# Schematic.net
KiCad netlist of a schematic drawn in EAGLE
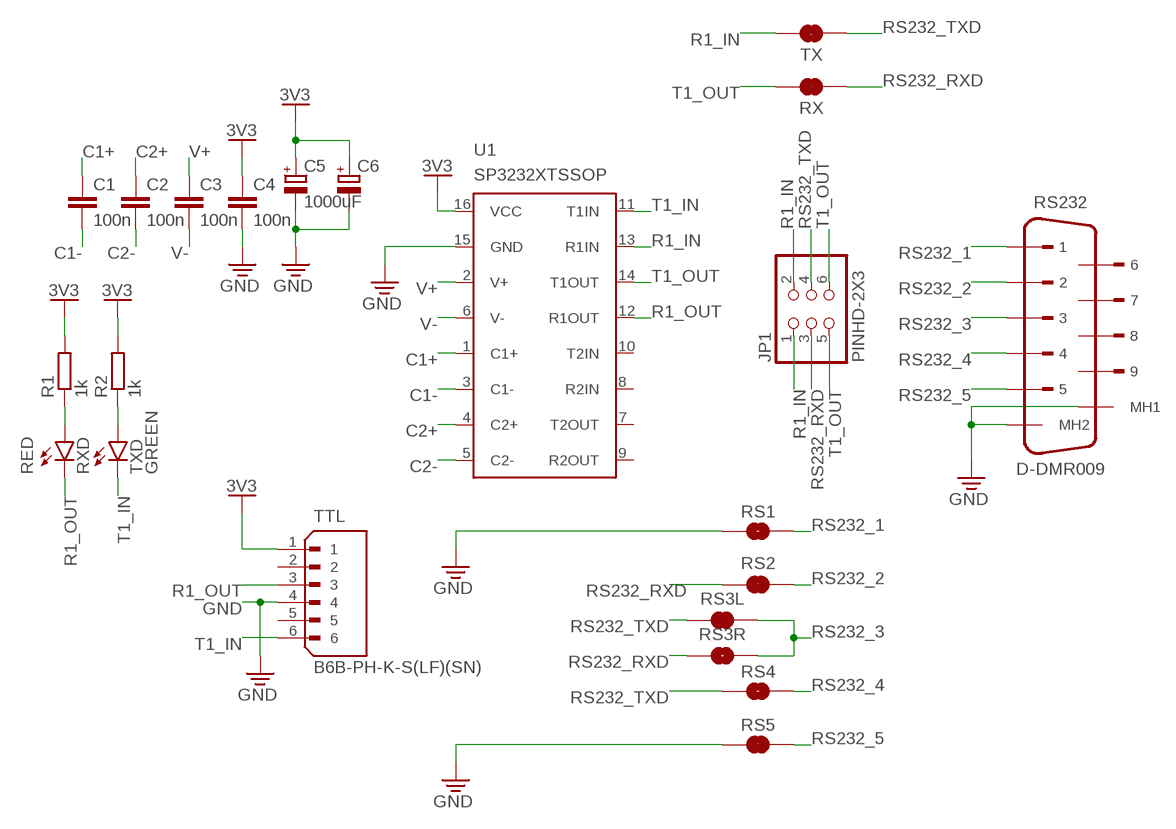
[diagram p0: schematic, sheet 1]

(export (version "E")
  (design (tool "Eeschema 10.0.6"))
  (components
    (comp (ref "C1")
      (value "100n")
      (footprint "eagle-import:C0402")
      (libsource (lib "eagle-import") (part "C-EUC0402"))
    )
    (comp (ref "C2")
      (value "100n")
      (footprint "eagle-import:C0402")
      (libsource (lib "eagle-import") (part "C-EUC0402"))
    )
    (comp (ref "C3")
      (value "100n")
      (footprint "eagle-import:C0402")
      (libsource (lib "eagle-import") (part "C-EUC0402"))
    )
    (comp (ref "C4")
      (value "100n")
      (footprint "eagle-import:C0402")
      (libsource (lib "eagle-import") (part "C-EUC0402"))
    )
    (comp (ref "C5")
      (value "1000uF")
      (footprint "eagle-import:140CLH-1010")
      (libsource (lib "eagle-import") (part "CPOL-EU140CLH-1010"))
    )
    (comp (ref "C6")
      (value "C-POL_RADIAL-11MM-DIA")
      (footprint "eagle-import:CAPPRD508W65D1000H1100B")
      (libsource (lib "eagle-import") (part "C-POLRADIAL-11MM-DIA_"))
    )
    (comp (ref "JP1")
      (value "PINHD-2X3")
      (footprint "eagle-import:2X03")
      (fields (field (name "MANUFACTURER") "Generic"))
      (libsource (lib "eagle-import") (part "PINHD-2X3"))
    )
    (comp (ref "R1")
      (value "1k")
      (footprint "eagle-import:R0402")
      (libsource (lib "eagle-import") (part "R-EU_R0402"))
    )
    (comp (ref "R2")
      (value "1k")
      (footprint "eagle-import:R0402")
      (libsource (lib "eagle-import") (part "R-EU_R0402"))
    )
    (comp (ref "RS1")
      (value "JUMPER-SMT_2_NO_SILK")
      (footprint "eagle-import:SMT-JUMPER_2_NO_SILK")
      (libsource (lib "eagle-import") (part "JUMPER-SMT_2_NO_SILK"))
    )
    (comp (ref "RS2")
      (value "JUMPER-SMT_2_NO_SILK")
      (footprint "eagle-import:SMT-JUMPER_2_NC_TRACE_SILK")
      (libsource (lib "eagle-import") (part "JUMPER-SMT_2_NC_TRACE_SILK"))
    )
    (comp (ref "RS3L")
      (value "JUMPER-SMT_2_NC_TRACE_SILK")
      (footprint "eagle-import:SMT-JUMPER_2_NC_TRACE_SILK")
      (libsource (lib "eagle-import") (part "JUMPER-SMT_2_NC_TRACE_SILK"))
    )
    (comp (ref "RS3R")
      (value "JUMPER-SMT_2_NC_TRACE_SILK")
      (footprint "eagle-import:SMT-JUMPER_2_NO_SILK")
      (libsource (lib "eagle-import") (part "JUMPER-SMT_2_NO_SILK"))
    )
    (comp (ref "RS4")
      (value "JUMPER-SMT_2_NO_SILK")
      (footprint "eagle-import:SMT-JUMPER_2_NO_SILK")
      (libsource (lib "eagle-import") (part "JUMPER-SMT_2_NO_SILK"))
    )
    (comp (ref "RS5")
      (value "JUMPER-SMT_2_NO_SILK")
      (footprint "eagle-import:SMT-JUMPER_2_NC_TRACE_SILK")
      (libsource (lib "eagle-import") (part "JUMPER-SMT_2_NC_TRACE_SILK"))
    )
    (comp (ref "RS232")
      (value "D-DMR009")
      (footprint "eagle-import:5747840-4")
      (fields (field (name "MANUFACTURER") "TE Connectivity") (field (name "MPN") "5747840-4"))
      (libsource (lib "eagle-import") (part "5747840{dblquote}"))
    )
    (comp (ref "RX")
      (value "JUMPER-SMT_2_NC_TRACE_SILK")
      (footprint "eagle-import:SMT-JUMPER_2_NC_TRACE_SILK")
      (libsource (lib "eagle-import") (part "JUMPER-SMT_2_NC_TRACE_SILK"))
    )
    (comp (ref "RXD")
      (value "RED")
      (footprint "eagle-import:CHIP-LED0603")
      (libsource (lib "eagle-import") (part "LEDCHIP-LED0603"))
    )
    (comp (ref "TTL")
      (value "B6B-PH-K-S(LF)(SN)")
      (footprint "eagle-import:JST_B6B-PH-K-S(LF)(SN)")
      (fields (field (name "MF") "JST Sales America Inc."))
      (libsource (lib "eagle-import") (part "B6B-PH-K-S(LF)(SN)"))
    )
    (comp (ref "TX")
      (value "JUMPER-SMT_2_NC_TRACE_SILK")
      (footprint "eagle-import:SMT-JUMPER_2_NC_TRACE_SILK")
      (libsource (lib "eagle-import") (part "JUMPER-SMT_2_NC_TRACE_SILK"))
    )
    (comp (ref "TXD")
      (value "GREEN")
      (footprint "eagle-import:CHIP-LED0603")
      (libsource (lib "eagle-import") (part "LEDCHIP-LED0603"))
    )
    (comp (ref "U1")
      (value "SP3232XTSSOP")
      (footprint "eagle-import:TSSOP16")
      (libsource (lib "eagle-import") (part "SP3232XTSSOP"))
    )
  )
  (nets
    (net (code "1") (name "/C1+") (class "Default")
      (node (ref "C1") (pin "1") (pinfunction "1_1") (pintype "passive"))
      (node (ref "U1") (pin "1") (pinfunction "C1+_1") (pintype "bidirectional"))
    )
    (net (code "2") (name "/C1-") (class "Default")
      (node (ref "C1") (pin "2") (pinfunction "2_2") (pintype "passive"))
      (node (ref "U1") (pin "3") (pinfunction "C1-_3") (pintype "bidirectional"))
    )
    (net (code "3") (name "/C2+") (class "Default")
      (node (ref "C2") (pin "1") (pinfunction "1_1") (pintype "passive"))
      (node (ref "U1") (pin "4") (pinfunction "C2+_4") (pintype "bidirectional"))
    )
    (net (code "4") (name "/C2-") (class "Default")
      (node (ref "C2") (pin "2") (pinfunction "2_2") (pintype "passive"))
      (node (ref "U1") (pin "5") (pinfunction "C2-_5") (pintype "bidirectional"))
    )
    (net (code "5") (name "/R1_IN") (class "Default")
      (node (ref "JP1") (pin "1") (pinfunction "1_1") (pintype "passive"))
      (node (ref "JP1") (pin "2") (pinfunction "2_2") (pintype "passive"))
      (node (ref "TX") (pin "2") (pinfunction "2_2") (pintype "passive"))
      (node (ref "U1") (pin "13") (pinfunction "R1IN_13") (pintype "input"))
    )
    (net (code "6") (name "/R1_OUT") (class "Default")
      (node (ref "RXD") (pin "C") (pinfunction "C_C") (pintype "passive"))
      (node (ref "TTL") (pin "3") (pinfunction "3_3") (pintype "passive"))
      (node (ref "U1") (pin "12") (pinfunction "R1OUT_12") (pintype "output"))
    )
    (net (code "7") (name "/RS232_1") (class "Default")
      (node (ref "RS1") (pin "2") (pinfunction "2_2") (pintype "passive"))
      (node (ref "RS232") (pin "1") (pinfunction "1_1") (pintype "passive"))
    )
    (net (code "8") (name "/RS232_2") (class "Default")
      (node (ref "RS2") (pin "2") (pinfunction "2_2") (pintype "passive"))
      (node (ref "RS232") (pin "2") (pinfunction "2_2") (pintype "passive"))
    )
    (net (code "9") (name "/RS232_3") (class "Default")
      (node (ref "RS232") (pin "3") (pinfunction "3_3") (pintype "passive"))
      (node (ref "RS3L") (pin "2") (pinfunction "2_2") (pintype "passive"))
      (node (ref "RS3R") (pin "2") (pinfunction "2_2") (pintype "passive"))
    )
    (net (code "10") (name "/RS232_4") (class "Default")
      (node (ref "RS232") (pin "4") (pinfunction "4_4") (pintype "passive"))
      (node (ref "RS4") (pin "2") (pinfunction "2_2") (pintype "passive"))
    )
    (net (code "11") (name "/RS232_5") (class "Default")
      (node (ref "RS232") (pin "5") (pinfunction "5_5") (pintype "passive"))
      (node (ref "RS5") (pin "2") (pinfunction "2_2") (pintype "passive"))
    )
    (net (code "12") (name "/RS232_RXD") (class "Default")
      (node (ref "JP1") (pin "3") (pinfunction "3_3") (pintype "passive"))
      (node (ref "RS2") (pin "1") (pinfunction "1_1") (pintype "passive"))
      (node (ref "RS3R") (pin "1") (pinfunction "1_1") (pintype "passive"))
      (node (ref "RX") (pin "1") (pinfunction "1_1") (pintype "passive"))
    )
    (net (code "13") (name "/RS232_TXD") (class "Default")
      (node (ref "JP1") (pin "4") (pinfunction "4_4") (pintype "passive"))
      (node (ref "RS3L") (pin "1") (pinfunction "1_1") (pintype "passive"))
      (node (ref "RS4") (pin "1") (pinfunction "1_1") (pintype "passive"))
      (node (ref "TX") (pin "1") (pinfunction "1_1") (pintype "passive"))
    )
    (net (code "14") (name "/T1_IN") (class "Default")
      (node (ref "TTL") (pin "6") (pinfunction "6_6") (pintype "passive"))
      (node (ref "TXD") (pin "C") (pinfunction "C_C") (pintype "passive"))
      (node (ref "U1") (pin "11") (pinfunction "T1IN_11") (pintype "input"))
    )
    (net (code "15") (name "/T1_OUT") (class "Default")
      (node (ref "JP1") (pin "5") (pinfunction "5_5") (pintype "passive"))
      (node (ref "JP1") (pin "6") (pinfunction "6_6") (pintype "passive"))
      (node (ref "RX") (pin "2") (pinfunction "2_2") (pintype "passive"))
      (node (ref "U1") (pin "14") (pinfunction "T1OUT_14") (pintype "output"))
    )
    (net (code "16") (name "/V+") (class "Default")
      (node (ref "C3") (pin "1") (pinfunction "1_1") (pintype "passive"))
      (node (ref "U1") (pin "2") (pinfunction "V+_2") (pintype "power_in"))
    )
    (net (code "17") (name "/V-") (class "Default")
      (node (ref "C3") (pin "2") (pinfunction "2_2") (pintype "passive"))
      (node (ref "U1") (pin "6") (pinfunction "V-_6") (pintype "power_in"))
    )
    (net (code "18") (name "3V3") (class "Default")
      (node (ref "C4") (pin "1") (pinfunction "1_1") (pintype "passive"))
      (node (ref "C5") (pin "+") (pinfunction "+_+") (pintype "passive"))
      (node (ref "C6") (pin "1") (pinfunction "+_1") (pintype "passive"))
      (node (ref "R1") (pin "2") (pinfunction "2_2") (pintype "passive"))
      (node (ref "R2") (pin "2") (pinfunction "2_2") (pintype "passive"))
      (node (ref "TTL") (pin "1") (pinfunction "1_1") (pintype "passive"))
      (node (ref "U1") (pin "16") (pinfunction "VCC_16") (pintype "power_in"))
    )
    (net (code "19") (name "GND") (class "Default")
      (node (ref "C4") (pin "2") (pinfunction "2_2") (pintype "passive"))
      (node (ref "C5") (pin "-") (pinfunction "-_-") (pintype "passive"))
      (node (ref "C6") (pin "2") (pinfunction "-_2") (pintype "passive"))
      (node (ref "RS1") (pin "1") (pinfunction "1_1") (pintype "passive"))
      (node (ref "RS232") (pin "MH1") (pinfunction "MH2_MH1") (pintype "power_in"))
      (node (ref "RS232") (pin "MH2") (pinfunction "MH1_MH2") (pintype "power_in"))
      (node (ref "RS5") (pin "1") (pinfunction "1_1") (pintype "passive"))
      (node (ref "TTL") (pin "4") (pinfunction "4_4") (pintype "passive"))
      (node (ref "U1") (pin "15") (pinfunction "GND_15") (pintype "power_in"))
    )
    (net (code "20") (name "Net-(R1-Pad1)") (class "Default")
      (node (ref "R1") (pin "1") (pinfunction "1_1") (pintype "passive"))
      (node (ref "RXD") (pin "A") (pinfunction "A_A") (pintype "passive"))
    )
    (net (code "21") (name "Net-(R2-Pad1)") (class "Default")
      (node (ref "R2") (pin "1") (pinfunction "1_1") (pintype "passive"))
      (node (ref "TXD") (pin "A") (pinfunction "A_A") (pintype "passive"))
    )
    (net (code "22") (name "unconnected-(RS232-Pad6)") (class "Default")
      (node (ref "RS232") (pin "6") (pinfunction "6_6") (pintype "passive"))
    )
    (net (code "23") (name "unconnected-(RS232-Pad7)") (class "Default")
      (node (ref "RS232") (pin "7") (pinfunction "7_7") (pintype "passive"))
    )
    (net (code "24") (name "unconnected-(RS232-Pad8)") (class "Default")
      (node (ref "RS232") (pin "8") (pinfunction "8_8") (pintype "passive"))
    )
    (net (code "25") (name "unconnected-(RS232-Pad9)") (class "Default")
      (node (ref "RS232") (pin "9") (pinfunction "9_9") (pintype "passive"))
    )
    (net (code "26") (name "unconnected-(TTL-Pad2)") (class "Default")
      (node (ref "TTL") (pin "2") (pinfunction "2_2") (pintype "passive"))
    )
    (net (code "27") (name "unconnected-(TTL-Pad5)") (class "Default")
      (node (ref "TTL") (pin "5") (pinfunction "5_5") (pintype "passive"))
    )
    (net (code "28") (name "unconnected-(U1-R2IN-Pad8)") (class "Default")
      (node (ref "U1") (pin "8") (pinfunction "R2IN_8") (pintype "input"))
    )
    (net (code "29") (name "unconnected-(U1-R2OUT-Pad9)") (class "Default")
      (node (ref "U1") (pin "9") (pinfunction "R2OUT_9") (pintype "output"))
    )
    (net (code "30") (name "unconnected-(U1-T2IN-Pad10)") (class "Default")
      (node (ref "U1") (pin "10") (pinfunction "T2IN_10") (pintype "input"))
    )
    (net (code "31") (name "unconnected-(U1-T2OUT-Pad7)") (class "Default")
      (node (ref "U1") (pin "7") (pinfunction "T2OUT_7") (pintype "output"))
    )
  )
)
